# Scheme1.net
KiCad netlist of a schematic drawn in Altium Designer
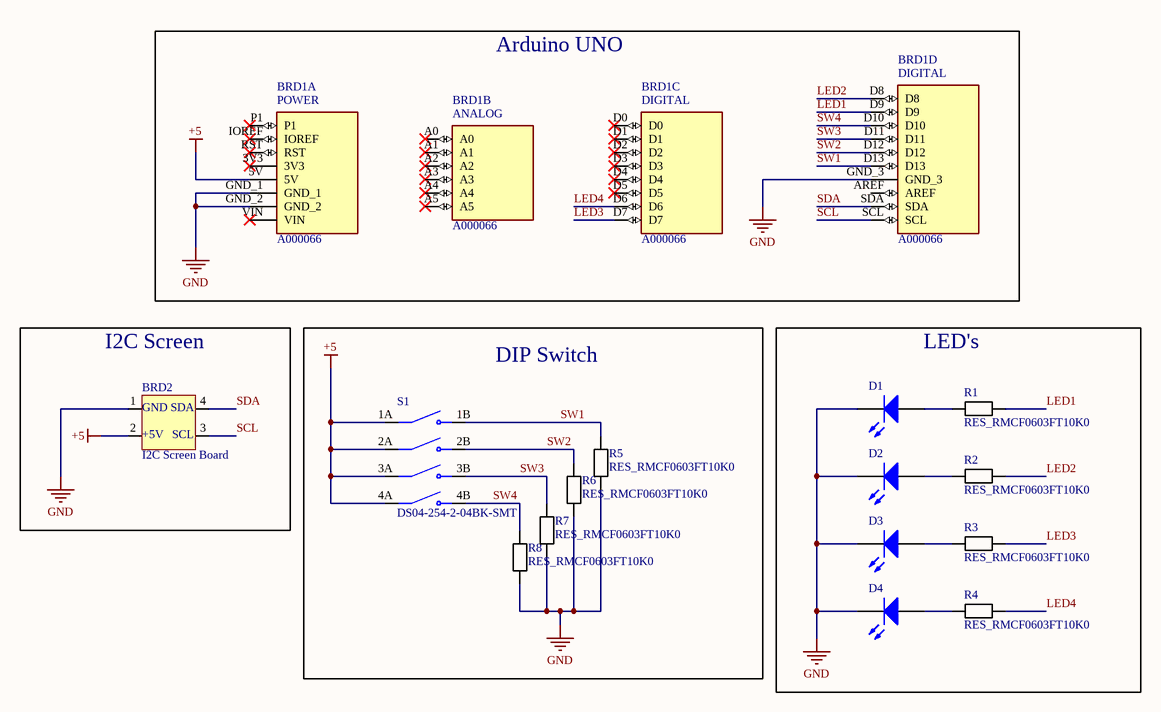
[diagram p0: Scheme1.SchDoc]

(export (version "E")
  (design (tool "Eeschema 10.0.6"))
  (components
    (comp (ref "BRD1")
      (value "A000066")
      (footprint "ARDUINO_A000066")
      (description "Microcontroller board based on the ATmega328P.")
      (fields (field (name "MF") "Arduino") (field (name "MP") "Arduino Uno Rev3"))
      (libsource (lib "SkillDevSchemLib") (part "A000066"))
    )
    (comp (ref "BRD2")
      (value "I2C Screen Board")
      (footprint "SSD1306 I2C Screen")
      (libsource (lib "SkillDevSchemLib") (part "SSD1306 I2C Screen"))
    )
    (comp (ref "D1")
      (value "Light-Emitting Diode")
      (footprint "Harvatek 0603 LED")
      (libsource (lib "Simulation Generic Components") (part "LED"))
    )
    (comp (ref "D2")
      (value "Light-Emitting Diode")
      (footprint "Harvatek 0603 LED")
      (libsource (lib "Simulation Generic Components") (part "LED"))
    )
    (comp (ref "D3")
      (value "Light-Emitting Diode")
      (footprint "Harvatek 0603 LED")
      (libsource (lib "Simulation Generic Components") (part "LED"))
    )
    (comp (ref "D4")
      (value "Light-Emitting Diode")
      (footprint "Harvatek 0603 LED")
      (libsource (lib "Simulation Generic Components") (part "LED"))
    )
    (comp (ref "R1")
      (value "RES_RMCF0603FT10K0")
      (footprint "SkillDevPCBLib:RES_RMCF0603")
      (description "RES 10K OHM 1% 1/10W 0603")
      (fields
        (field (name "PART NUMBER") "RMCF0603FT10K0")
        (field (name "MANUFACTURER") "Stackpole Electronics Inc")
      )
      (libsource (lib "SkillDevSchemLib") (part "RES_RMCF0603FT10K0"))
    )
    (comp (ref "R2")
      (value "RES_RMCF0603FT10K0")
      (footprint "SkillDevPCBLib:RES_RMCF0603")
      (description "RES 10K OHM 1% 1/10W 0603")
      (fields
        (field (name "PART NUMBER") "RMCF0603FT10K0")
        (field (name "MANUFACTURER") "Stackpole Electronics Inc")
      )
      (libsource (lib "SkillDevSchemLib") (part "RES_RMCF0603FT10K0"))
    )
    (comp (ref "R3")
      (value "RES_RMCF0603FT10K0")
      (footprint "SkillDevPCBLib:RES_RMCF0603")
      (description "RES 10K OHM 1% 1/10W 0603")
      (fields
        (field (name "PART NUMBER") "RMCF0603FT10K0")
        (field (name "MANUFACTURER") "Stackpole Electronics Inc")
      )
      (libsource (lib "SkillDevSchemLib") (part "RES_RMCF0603FT10K0"))
    )
    (comp (ref "R4")
      (value "RES_RMCF0603FT10K0")
      (footprint "SkillDevPCBLib:RES_RMCF0603")
      (description "RES 10K OHM 1% 1/10W 0603")
      (fields
        (field (name "PART NUMBER") "RMCF0603FT10K0")
        (field (name "MANUFACTURER") "Stackpole Electronics Inc")
      )
      (libsource (lib "SkillDevSchemLib") (part "RES_RMCF0603FT10K0"))
    )
    (comp (ref "R5")
      (value "RES_RMCF0603FT10K0")
      (footprint "SkillDevPCBLib:RES_RMCF0603")
      (description "RES 10K OHM 1% 1/10W 0603")
      (fields
        (field (name "PART NUMBER") "RMCF0603FT10K0")
        (field (name "MANUFACTURER") "Stackpole Electronics Inc")
      )
      (libsource (lib "SkillDevSchemLib") (part "RES_RMCF0603FT10K0"))
    )
    (comp (ref "R6")
      (value "RES_RMCF0603FT10K0")
      (footprint "SkillDevPCBLib:RES_RMCF0603")
      (description "RES 10K OHM 1% 1/10W 0603")
      (fields
        (field (name "PART NUMBER") "RMCF0603FT10K0")
        (field (name "MANUFACTURER") "Stackpole Electronics Inc")
      )
      (libsource (lib "SkillDevSchemLib") (part "RES_RMCF0603FT10K0"))
    )
    (comp (ref "R7")
      (value "RES_RMCF0603FT10K0")
      (footprint "SkillDevPCBLib:RES_RMCF0603")
      (description "RES 10K OHM 1% 1/10W 0603")
      (fields
        (field (name "PART NUMBER") "RMCF0603FT10K0")
        (field (name "MANUFACTURER") "Stackpole Electronics Inc")
      )
      (libsource (lib "SkillDevSchemLib") (part "RES_RMCF0603FT10K0"))
    )
    (comp (ref "R8")
      (value "RES_RMCF0603FT10K0")
      (footprint "SkillDevPCBLib:RES_RMCF0603")
      (description "RES 10K OHM 1% 1/10W 0603")
      (fields
        (field (name "PART NUMBER") "RMCF0603FT10K0")
        (field (name "MANUFACTURER") "Stackpole Electronics Inc")
      )
      (libsource (lib "SkillDevSchemLib") (part "RES_RMCF0603FT10K0"))
    )
    (comp (ref "S1")
      (value "DS04-254-2-04BK-SMT")
      (footprint "SW_DS04-254-2-04BK-SMT")
      (description "4 Position, Surface Mount, 2.54 mm Pitch, Flat Slide Actuator, Flat Bottom, SMT Pin, DIP Switch")
      (fields (field (name "MF") "CUI Devices"))
      (libsource (lib "DS04-254-2-04BK-SMT") (part "DS04-254-2-04BK-SMT"))
    )
  )
  (nets
    (net (code "1") (name "+5") (class "Default")
      (node (ref "BRD1") (pin "5V") (pinfunction "5V_5V") (pintype "power_in"))
      (node (ref "BRD2") (pin "2") (pintype "power_in"))
      (node (ref "S1") (pin "1A") (pinfunction "COM1_1A") (pintype "passive"))
      (node (ref "S1") (pin "2A") (pinfunction "COM2_2A") (pintype "passive"))
      (node (ref "S1") (pin "3A") (pinfunction "COM3_3A") (pintype "passive"))
      (node (ref "S1") (pin "4A") (pinfunction "COM4_4A") (pintype "passive"))
    )
    (net (code "2") (name "/LED1") (class "Default")
      (node (ref "BRD1") (pin "D9") (pinfunction "D9_D9") (pintype "bidirectional"))
      (node (ref "R1") (pin "2") (pintype "passive"))
    )
    (net (code "3") (name "/LED2") (class "Default")
      (node (ref "BRD1") (pin "D8") (pinfunction "D8_D8") (pintype "bidirectional"))
      (node (ref "R2") (pin "2") (pintype "passive"))
    )
    (net (code "4") (name "/LED3") (class "Default")
      (node (ref "BRD1") (pin "D7") (pinfunction "D7_D7") (pintype "bidirectional"))
      (node (ref "R3") (pin "2") (pintype "passive"))
    )
    (net (code "5") (name "/LED4") (class "Default")
      (node (ref "BRD1") (pin "D6") (pinfunction "D6_D6") (pintype "bidirectional"))
      (node (ref "R4") (pin "2") (pintype "passive"))
    )
    (net (code "6") (name "/SCL") (class "Default")
      (node (ref "BRD1") (pin "SCL") (pinfunction "SCL_SCL") (pintype "bidirectional"))
      (node (ref "BRD2") (pin "3") (pintype "passive"))
    )
    (net (code "7") (name "/SDA") (class "Default")
      (node (ref "BRD1") (pin "SDA") (pinfunction "SDA_SDA") (pintype "bidirectional"))
      (node (ref "BRD2") (pin "4") (pintype "passive"))
    )
    (net (code "8") (name "/SW1") (class "Default")
      (node (ref "BRD1") (pin "D13") (pinfunction "D13_D13") (pintype "bidirectional"))
      (node (ref "R5") (pin "2") (pintype "passive"))
      (node (ref "S1") (pin "1B") (pinfunction "NO1_1B") (pintype "passive"))
    )
    (net (code "9") (name "/SW2") (class "Default")
      (node (ref "BRD1") (pin "D12") (pinfunction "D12_D12") (pintype "bidirectional"))
      (node (ref "R6") (pin "2") (pintype "passive"))
      (node (ref "S1") (pin "2B") (pinfunction "NO2_2B") (pintype "passive"))
    )
    (net (code "10") (name "/SW3") (class "Default")
      (node (ref "BRD1") (pin "D11") (pinfunction "D11_D11") (pintype "bidirectional"))
      (node (ref "R7") (pin "2") (pintype "passive"))
      (node (ref "S1") (pin "3B") (pinfunction "NO3_3B") (pintype "passive"))
    )
    (net (code "11") (name "/SW4") (class "Default")
      (node (ref "BRD1") (pin "D10") (pinfunction "D10_D10") (pintype "bidirectional"))
      (node (ref "R8") (pin "2") (pintype "passive"))
      (node (ref "S1") (pin "4B") (pinfunction "NO4_4B") (pintype "passive"))
    )
    (net (code "12") (name "GND") (class "Default")
      (node (ref "BRD1") (pin "GND_1") (pinfunction "GND_1_GND_1") (pintype "power_in"))
      (node (ref "BRD1") (pin "GND_2") (pinfunction "GND_2_GND_2") (pintype "power_in"))
      (node (ref "BRD1") (pin "GND_3") (pinfunction "GND_3_GND_3") (pintype "power_in"))
      (node (ref "BRD2") (pin "1") (pintype "power_in"))
      (node (ref "D1") (pin "2") (pinfunction "K_2") (pintype "passive"))
      (node (ref "D2") (pin "2") (pinfunction "K_2") (pintype "passive"))
      (node (ref "D3") (pin "2") (pinfunction "K_2") (pintype "passive"))
      (node (ref "D4") (pin "2") (pinfunction "K_2") (pintype "passive"))
      (node (ref "R5") (pin "1") (pintype "passive"))
      (node (ref "R6") (pin "1") (pintype "passive"))
      (node (ref "R7") (pin "1") (pintype "passive"))
      (node (ref "R8") (pin "1") (pintype "passive"))
    )
    (net (code "13") (name "Net-(D1-A)") (class "Default")
      (node (ref "D1") (pin "1") (pinfunction "A_1") (pintype "passive"))
      (node (ref "R1") (pin "1") (pintype "passive"))
    )
    (net (code "14") (name "Net-(D2-A)") (class "Default")
      (node (ref "D2") (pin "1") (pinfunction "A_1") (pintype "passive"))
      (node (ref "R2") (pin "1") (pintype "passive"))
    )
    (net (code "15") (name "Net-(D3-A)") (class "Default")
      (node (ref "D3") (pin "1") (pinfunction "A_1") (pintype "passive"))
      (node (ref "R3") (pin "1") (pintype "passive"))
    )
    (net (code "16") (name "Net-(D4-A)") (class "Default")
      (node (ref "D4") (pin "1") (pinfunction "A_1") (pintype "passive"))
      (node (ref "R4") (pin "1") (pintype "passive"))
    )
    (net (code "17") (name "unconnected-(BRD1-Pad3V3)") (class "Default")
      (node (ref "BRD1") (pin "3V3") (pinfunction "3V3_3V3") (pintype "power_in+no_connect"))
    )
    (net (code "18") (name "unconnected-(BRD1-PadA0)") (class "Default")
      (node (ref "BRD1") (pin "A0") (pinfunction "A0_A0") (pintype "bidirectional+no_connect"))
    )
    (net (code "19") (name "unconnected-(BRD1-PadA1)") (class "Default")
      (node (ref "BRD1") (pin "A1") (pinfunction "A1_A1") (pintype "bidirectional+no_connect"))
    )
    (net (code "20") (name "unconnected-(BRD1-PadA2)") (class "Default")
      (node (ref "BRD1") (pin "A2") (pinfunction "A2_A2") (pintype "bidirectional+no_connect"))
    )
    (net (code "21") (name "unconnected-(BRD1-PadA3)") (class "Default")
      (node (ref "BRD1") (pin "A3") (pinfunction "A3_A3") (pintype "bidirectional+no_connect"))
    )
    (net (code "22") (name "unconnected-(BRD1-PadA4)") (class "Default")
      (node (ref "BRD1") (pin "A4") (pinfunction "A4_A4") (pintype "bidirectional+no_connect"))
    )
    (net (code "23") (name "unconnected-(BRD1-PadA5)") (class "Default")
      (node (ref "BRD1") (pin "A5") (pinfunction "A5_A5") (pintype "bidirectional+no_connect"))
    )
    (net (code "24") (name "unconnected-(BRD1-PadAREF)") (class "Default")
      (node (ref "BRD1") (pin "AREF") (pinfunction "AREF_AREF") (pintype "bidirectional"))
    )
    (net (code "25") (name "unconnected-(BRD1-PadD0)") (class "Default")
      (node (ref "BRD1") (pin "D0") (pinfunction "D0_D0") (pintype "bidirectional+no_connect"))
    )
    (net (code "26") (name "unconnected-(BRD1-PadD1)") (class "Default")
      (node (ref "BRD1") (pin "D1") (pinfunction "D1_D1") (pintype "bidirectional+no_connect"))
    )
    (net (code "27") (name "unconnected-(BRD1-PadD2)") (class "Default")
      (node (ref "BRD1") (pin "D2") (pinfunction "D2_D2") (pintype "bidirectional+no_connect"))
    )
    (net (code "28") (name "unconnected-(BRD1-PadD3)") (class "Default")
      (node (ref "BRD1") (pin "D3") (pinfunction "D3_D3") (pintype "bidirectional+no_connect"))
    )
    (net (code "29") (name "unconnected-(BRD1-PadD4)") (class "Default")
      (node (ref "BRD1") (pin "D4") (pinfunction "D4_D4") (pintype "bidirectional+no_connect"))
    )
    (net (code "30") (name "unconnected-(BRD1-PadD5)") (class "Default")
      (node (ref "BRD1") (pin "D5") (pinfunction "D5_D5") (pintype "bidirectional+no_connect"))
    )
    (net (code "31") (name "unconnected-(BRD1-PadIOREF)") (class "Default")
      (node (ref "BRD1") (pin "IOREF") (pinfunction "IOREF_IOREF") (pintype "bidirectional+no_connect"))
    )
    (net (code "32") (name "unconnected-(BRD1-PadP1)") (class "Default")
      (node (ref "BRD1") (pin "P1") (pinfunction "P1_P1") (pintype "bidirectional+no_connect"))
    )
    (net (code "33") (name "unconnected-(BRD1-PadRST)") (class "Default")
      (node (ref "BRD1") (pin "RST") (pinfunction "RST_RST") (pintype "bidirectional+no_connect"))
    )
    (net (code "34") (name "unconnected-(BRD1-PadVIN)") (class "Default")
      (node (ref "BRD1") (pin "VIN") (pinfunction "VIN_VIN") (pintype "power_in+no_connect"))
    )
  )
)
